# IC_DISPLAY_SCHE.net
KiCad netlist of a schematic drawn in Altium Designer
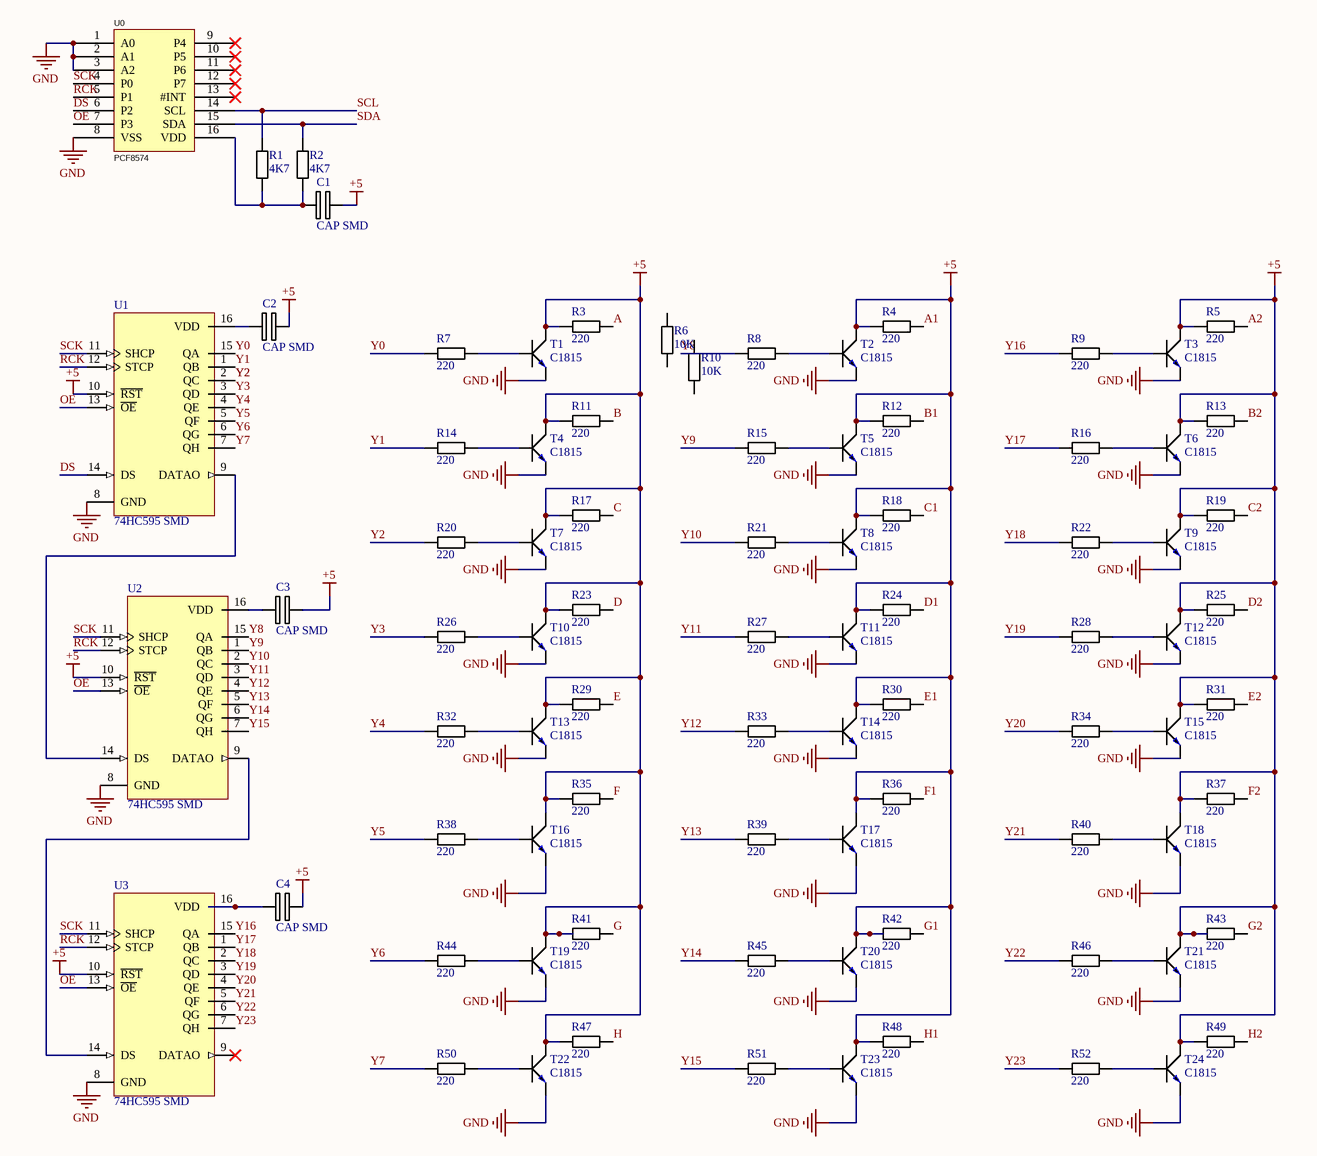
[diagram p0: IC_DISPLAY_SCHE.SchDoc]

(export (version "E")
  (design (tool "Eeschema 10.0.6"))
  (components
    (comp (ref "C1")
      (value "CAP SMD")
      (footprint "C-0805")
      (description "Capacitor Polarised")
      (fields
        (field (name "MANUFACTURER_PART_NUMBER") "TAJC227K006RNJV")
        (field (name "MOUSER PART NUMBER") "581-TAJC227K006RNJV")
      )
      (libsource (lib "MAIN1.2.3.4") (part "CAP SMD"))
    )
    (comp (ref "C2")
      (value "CAP SMD")
      (footprint "C-0805")
      (description "Capacitor Polarised")
      (fields
        (field (name "MANUFACTURER_PART_NUMBER") "TAJC227K006RNJV")
        (field (name "MOUSER PART NUMBER") "581-TAJC227K006RNJV")
      )
      (libsource (lib "MAIN1.2.3.4") (part "CAP SMD"))
    )
    (comp (ref "C3")
      (value "CAP SMD")
      (footprint "C-0805")
      (description "Capacitor Polarised")
      (fields
        (field (name "MANUFACTURER_PART_NUMBER") "TAJC227K006RNJV")
        (field (name "MOUSER PART NUMBER") "581-TAJC227K006RNJV")
      )
      (libsource (lib "MAIN1.2.3.4") (part "CAP SMD"))
    )
    (comp (ref "C4")
      (value "CAP SMD")
      (footprint "C-0805")
      (description "Capacitor Polarised")
      (fields
        (field (name "MANUFACTURER_PART_NUMBER") "TAJC227K006RNJV")
        (field (name "MOUSER PART NUMBER") "581-TAJC227K006RNJV")
      )
      (libsource (lib "MAIN1.2.3.4") (part "CAP SMD"))
    )
    (comp (ref "R1")
      (value "4K7")
      (footprint "Resistor 0805")
      (description "Resistor")
      (libsource (lib "MAIN1.2.3.4") (part "Resistor"))
    )
    (comp (ref "R2")
      (value "4K7")
      (footprint "Resistor 0805")
      (description "Resistor")
      (libsource (lib "MAIN1.2.3.4") (part "Resistor"))
    )
    (comp (ref "R3")
      (value "220")
      (footprint "Resistor 0805")
      (description "Resistor")
      (libsource (lib "MAIN1.2.3") (part "Resistor"))
    )
    (comp (ref "R4")
      (value "220")
      (footprint "Resistor 0805")
      (description "Resistor")
      (libsource (lib "MAIN1.2.3") (part "Resistor"))
    )
    (comp (ref "R5")
      (value "220")
      (footprint "Resistor 0805")
      (description "Resistor")
      (libsource (lib "MAIN1.2.3") (part "Resistor"))
    )
    (comp (ref "R6")
      (value "10K")
      (footprint "RES Axial 0.5W_10.16mm")
      (description "Resistor")
      (libsource (lib "MAIN1.2.3.4") (part "Resistor"))
    )
    (comp (ref "R7")
      (value "220")
      (footprint "Resistor 0805")
      (description "Resistor")
      (libsource (lib "MAIN1.2.3") (part "Resistor"))
    )
    (comp (ref "R8")
      (value "220")
      (footprint "Resistor 0805")
      (description "Resistor")
      (libsource (lib "MAIN1.2.3") (part "Resistor"))
    )
    (comp (ref "R9")
      (value "220")
      (footprint "Resistor 0805")
      (description "Resistor")
      (libsource (lib "MAIN1.2.3") (part "Resistor"))
    )
    (comp (ref "R10")
      (value "10K")
      (footprint "RES Axial 0.5W_10.16mm")
      (description "Resistor")
      (libsource (lib "MAIN1.2.3.4") (part "Resistor"))
    )
    (comp (ref "R11")
      (value "220")
      (footprint "Resistor 0805")
      (description "Resistor")
      (libsource (lib "MAIN1.2.3") (part "Resistor"))
    )
    (comp (ref "R12")
      (value "220")
      (footprint "Resistor 0805")
      (description "Resistor")
      (libsource (lib "MAIN1.2.3") (part "Resistor"))
    )
    (comp (ref "R13")
      (value "220")
      (footprint "Resistor 0805")
      (description "Resistor")
      (libsource (lib "MAIN1.2.3") (part "Resistor"))
    )
    (comp (ref "R14")
      (value "220")
      (footprint "Resistor 0805")
      (description "Resistor")
      (libsource (lib "MAIN1.2.3") (part "Resistor"))
    )
    (comp (ref "R15")
      (value "220")
      (footprint "Resistor 0805")
      (description "Resistor")
      (libsource (lib "MAIN1.2.3") (part "Resistor"))
    )
    (comp (ref "R16")
      (value "220")
      (footprint "Resistor 0805")
      (description "Resistor")
      (libsource (lib "MAIN1.2.3") (part "Resistor"))
    )
    (comp (ref "R17")
      (value "220")
      (footprint "Resistor 0805")
      (description "Resistor")
      (libsource (lib "MAIN1.2.3") (part "Resistor"))
    )
    (comp (ref "R18")
      (value "220")
      (footprint "Resistor 0805")
      (description "Resistor")
      (libsource (lib "MAIN1.2.3") (part "Resistor"))
    )
    (comp (ref "R19")
      (value "220")
      (footprint "Resistor 0805")
      (description "Resistor")
      (libsource (lib "MAIN1.2.3") (part "Resistor"))
    )
    (comp (ref "R20")
      (value "220")
      (footprint "Resistor 0805")
      (description "Resistor")
      (libsource (lib "MAIN1.2.3") (part "Resistor"))
    )
    (comp (ref "R21")
      (value "220")
      (footprint "Resistor 0805")
      (description "Resistor")
      (libsource (lib "MAIN1.2.3") (part "Resistor"))
    )
    (comp (ref "R22")
      (value "220")
      (footprint "Resistor 0805")
      (description "Resistor")
      (libsource (lib "MAIN1.2.3") (part "Resistor"))
    )
    (comp (ref "R23")
      (value "220")
      (footprint "Resistor 0805")
      (description "Resistor")
      (libsource (lib "MAIN1.2.3") (part "Resistor"))
    )
    (comp (ref "R24")
      (value "220")
      (footprint "Resistor 0805")
      (description "Resistor")
      (libsource (lib "MAIN1.2.3") (part "Resistor"))
    )
    (comp (ref "R25")
      (value "220")
      (footprint "Resistor 0805")
      (description "Resistor")
      (libsource (lib "MAIN1.2.3") (part "Resistor"))
    )
    (comp (ref "R26")
      (value "220")
      (footprint "Resistor 0805")
      (description "Resistor")
      (libsource (lib "MAIN1.2.3") (part "Resistor"))
    )
    (comp (ref "R27")
      (value "220")
      (footprint "Resistor 0805")
      (description "Resistor")
      (libsource (lib "MAIN1.2.3") (part "Resistor"))
    )
    (comp (ref "R28")
      (value "220")
      (footprint "Resistor 0805")
      (description "Resistor")
      (libsource (lib "MAIN1.2.3") (part "Resistor"))
    )
    (comp (ref "R29")
      (value "220")
      (footprint "Resistor 0805")
      (description "Resistor")
      (libsource (lib "MAIN1.2.3") (part "Resistor"))
    )
    (comp (ref "R30")
      (value "220")
      (footprint "Resistor 0805")
      (description "Resistor")
      (libsource (lib "MAIN1.2.3") (part "Resistor"))
    )
    (comp (ref "R31")
      (value "220")
      (footprint "Resistor 0805")
      (description "Resistor")
      (libsource (lib "MAIN1.2.3") (part "Resistor"))
    )
    (comp (ref "R32")
      (value "220")
      (footprint "Resistor 0805")
      (description "Resistor")
      (libsource (lib "MAIN1.2.3") (part "Resistor"))
    )
    (comp (ref "R33")
      (value "220")
      (footprint "Resistor 0805")
      (description "Resistor")
      (libsource (lib "MAIN1.2.3") (part "Resistor"))
    )
    (comp (ref "R34")
      (value "220")
      (footprint "Resistor 0805")
      (description "Resistor")
      (libsource (lib "MAIN1.2.3") (part "Resistor"))
    )
    (comp (ref "R35")
      (value "220")
      (footprint "Resistor 0805")
      (description "Resistor")
      (libsource (lib "MAIN1.2.3") (part "Resistor"))
    )
    (comp (ref "R36")
      (value "220")
      (footprint "Resistor 0805")
      (description "Resistor")
      (libsource (lib "MAIN1.2.3") (part "Resistor"))
    )
    (comp (ref "R37")
      (value "220")
      (footprint "Resistor 0805")
      (description "Resistor")
      (libsource (lib "MAIN1.2.3") (part "Resistor"))
    )
    (comp (ref "R38")
      (value "220")
      (footprint "Resistor 0805")
      (description "Resistor")
      (libsource (lib "MAIN1.2.3") (part "Resistor"))
    )
    (comp (ref "R39")
      (value "220")
      (footprint "Resistor 0805")
      (description "Resistor")
      (libsource (lib "MAIN1.2.3") (part "Resistor"))
    )
    (comp (ref "R40")
      (value "220")
      (footprint "Resistor 0805")
      (description "Resistor")
      (libsource (lib "MAIN1.2.3") (part "Resistor"))
    )
    (comp (ref "R41")
      (value "220")
      (footprint "Resistor 0805")
      (description "Resistor")
      (libsource (lib "MAIN1.2.3") (part "Resistor"))
    )
    (comp (ref "R42")
      (value "220")
      (footprint "Resistor 0805")
      (description "Resistor")
      (libsource (lib "MAIN1.2.3") (part "Resistor"))
    )
    (comp (ref "R43")
      (value "220")
      (footprint "Resistor 0805")
      (description "Resistor")
      (libsource (lib "MAIN1.2.3") (part "Resistor"))
    )
    (comp (ref "R44")
      (value "220")
      (footprint "Resistor 0805")
      (description "Resistor")
      (libsource (lib "MAIN1.2.3") (part "Resistor"))
    )
    (comp (ref "R45")
      (value "220")
      (footprint "Resistor 0805")
      (description "Resistor")
      (libsource (lib "MAIN1.2.3") (part "Resistor"))
    )
    (comp (ref "R46")
      (value "220")
      (footprint "Resistor 0805")
      (description "Resistor")
      (libsource (lib "MAIN1.2.3") (part "Resistor"))
    )
    (comp (ref "R47")
      (value "220")
      (footprint "Resistor 0805")
      (description "Resistor")
      (libsource (lib "MAIN1.2.3") (part "Resistor"))
    )
    (comp (ref "R48")
      (value "220")
      (footprint "Resistor 0805")
      (description "Resistor")
      (libsource (lib "MAIN1.2.3") (part "Resistor"))
    )
    (comp (ref "R49")
      (value "220")
      (footprint "Resistor 0805")
      (description "Resistor")
      (libsource (lib "MAIN1.2.3") (part "Resistor"))
    )
    (comp (ref "R50")
      (value "220")
      (footprint "Resistor 0805")
      (description "Resistor")
      (libsource (lib "MAIN1.2.3") (part "Resistor"))
    )
    (comp (ref "R51")
      (value "220")
      (footprint "Resistor 0805")
      (description "Resistor")
      (libsource (lib "MAIN1.2.3") (part "Resistor"))
    )
    (comp (ref "R52")
      (value "220")
      (footprint "Resistor 0805")
      (description "Resistor")
      (libsource (lib "MAIN1.2.3") (part "Resistor"))
    )
    (comp (ref "T1")
      (value "C1815")
      (footprint "SOT23-BCE")
      (description "Bipolar Transistors - BJT NPN Epitaxial Sil")
      (libsource (lib "MAIN1.2.3") (part "2SC1815"))
    )
    (comp (ref "T2")
      (value "C1815")
      (footprint "SOT23-BCE")
      (description "Bipolar Transistors - BJT NPN Epitaxial Sil")
      (libsource (lib "MAIN1.2.3") (part "2SC1815"))
    )
    (comp (ref "T3")
      (value "C1815")
      (footprint "SOT23-BCE")
      (description "Bipolar Transistors - BJT NPN Epitaxial Sil")
      (libsource (lib "MAIN1.2.3") (part "2SC1815"))
    )
    (comp (ref "T4")
      (value "C1815")
      (footprint "SOT23-BCE")
      (description "Bipolar Transistors - BJT NPN Epitaxial Sil")
      (libsource (lib "MAIN1.2.3") (part "2SC1815"))
    )
    (comp (ref "T5")
      (value "C1815")
      (footprint "SOT23-BCE")
      (description "Bipolar Transistors - BJT NPN Epitaxial Sil")
      (libsource (lib "MAIN1.2.3") (part "2SC1815"))
    )
    (comp (ref "T6")
      (value "C1815")
      (footprint "SOT23-BCE")
      (description "Bipolar Transistors - BJT NPN Epitaxial Sil")
      (libsource (lib "MAIN1.2.3") (part "2SC1815"))
    )
    (comp (ref "T7")
      (value "C1815")
      (footprint "SOT23-BCE")
      (description "Bipolar Transistors - BJT NPN Epitaxial Sil")
      (libsource (lib "MAIN1.2.3") (part "2SC1815"))
    )
    (comp (ref "T8")
      (value "C1815")
      (footprint "SOT23-BCE")
      (description "Bipolar Transistors - BJT NPN Epitaxial Sil")
      (libsource (lib "MAIN1.2.3") (part "2SC1815"))
    )
    (comp (ref "T9")
      (value "C1815")
      (footprint "SOT23-BCE")
      (description "Bipolar Transistors - BJT NPN Epitaxial Sil")
      (libsource (lib "MAIN1.2.3") (part "2SC1815"))
    )
    (comp (ref "T10")
      (value "C1815")
      (footprint "SOT23-BCE")
      (description "Bipolar Transistors - BJT NPN Epitaxial Sil")
      (libsource (lib "MAIN1.2.3") (part "2SC1815"))
    )
    (comp (ref "T11")
      (value "C1815")
      (footprint "SOT23-BCE")
      (description "Bipolar Transistors - BJT NPN Epitaxial Sil")
      (libsource (lib "MAIN1.2.3") (part "2SC1815"))
    )
    (comp (ref "T12")
      (value "C1815")
      (footprint "SOT23-BCE")
      (description "Bipolar Transistors - BJT NPN Epitaxial Sil")
      (libsource (lib "MAIN1.2.3") (part "2SC1815"))
    )
    (comp (ref "T13")
      (value "C1815")
      (footprint "SOT23-BCE")
      (description "Bipolar Transistors - BJT NPN Epitaxial Sil")
      (libsource (lib "MAIN1.2.3") (part "2SC1815"))
    )
    (comp (ref "T14")
      (value "C1815")
      (footprint "SOT23-BCE")
      (description "Bipolar Transistors - BJT NPN Epitaxial Sil")
      (libsource (lib "MAIN1.2.3") (part "2SC1815"))
    )
    (comp (ref "T15")
      (value "C1815")
      (footprint "SOT23-BCE")
      (description "Bipolar Transistors - BJT NPN Epitaxial Sil")
      (libsource (lib "MAIN1.2.3") (part "2SC1815"))
    )
    (comp (ref "T16")
      (value "C1815")
      (footprint "SOT23-BCE")
      (description "Bipolar Transistors - BJT NPN Epitaxial Sil")
      (libsource (lib "MAIN1.2.3") (part "2SC1815"))
    )
    (comp (ref "T17")
      (value "C1815")
      (footprint "SOT23-BCE")
      (description "Bipolar Transistors - BJT NPN Epitaxial Sil")
      (libsource (lib "MAIN1.2.3") (part "2SC1815"))
    )
    (comp (ref "T18")
      (value "C1815")
      (footprint "SOT23-BCE")
      (description "Bipolar Transistors - BJT NPN Epitaxial Sil")
      (libsource (lib "MAIN1.2.3") (part "2SC1815"))
    )
    (comp (ref "T19")
      (value "C1815")
      (footprint "SOT23-BCE")
      (description "Bipolar Transistors - BJT NPN Epitaxial Sil")
      (libsource (lib "MAIN1.2.3") (part "2SC1815"))
    )
    (comp (ref "T20")
      (value "C1815")
      (footprint "SOT23-BCE")
      (description "Bipolar Transistors - BJT NPN Epitaxial Sil")
      (libsource (lib "MAIN1.2.3") (part "2SC1815"))
    )
    (comp (ref "T21")
      (value "C1815")
      (footprint "SOT23-BCE")
      (description "Bipolar Transistors - BJT NPN Epitaxial Sil")
      (libsource (lib "MAIN1.2.3") (part "2SC1815"))
    )
    (comp (ref "T22")
      (value "C1815")
      (footprint "SOT23-BCE")
      (description "Bipolar Transistors - BJT NPN Epitaxial Sil")
      (libsource (lib "MAIN1.2.3") (part "2SC1815"))
    )
    (comp (ref "T23")
      (value "C1815")
      (footprint "SOT23-BCE")
      (description "Bipolar Transistors - BJT NPN Epitaxial Sil")
      (libsource (lib "MAIN1.2.3") (part "2SC1815"))
    )
    (comp (ref "T24")
      (value "C1815")
      (footprint "SOT23-BCE")
      (description "Bipolar Transistors - BJT NPN Epitaxial Sil")
      (libsource (lib "MAIN1.2.3") (part "2SC1815"))
    )
    (comp (ref "U0")
      (value "PCF8574")
      (footprint "SOIC-16-pcf8574")
      (fields (field (name "MANUFACTURER") "NXP(恩智浦)") (field (name "MANUFACTURER PART") "PCF8574AT/3,518"))
      (libsource (lib "MAIN1.2.3.4") (part "PCF8574AT/3"))
    )
    (comp (ref "U1")
      (value "74HC595 SMD")
      (footprint "SOP 16")
      (description "Dán")
      (libsource (lib "Altium_Lib_by_KhueNguyenCreator") (part "74HC595 SMD"))
    )
    (comp (ref "U2")
      (value "74HC595 SMD")
      (footprint "SOP 16")
      (description "Dán")
      (libsource (lib "Altium_Lib_by_KhueNguyenCreator") (part "74HC595 SMD"))
    )
    (comp (ref "U3")
      (value "74HC595 SMD")
      (footprint "SOP 16")
      (description "Dán")
      (libsource (lib "Altium_Lib_by_KhueNguyenCreator") (part "74HC595 SMD"))
    )
  )
  (nets
    (net (code "1") (name "+5") (class "Default")
      (node (ref "C1") (pin "2") (pinfunction "-_2") (pintype "passive"))
      (node (ref "C2") (pin "2") (pinfunction "-_2") (pintype "passive"))
      (node (ref "C3") (pin "2") (pinfunction "-_2") (pintype "passive"))
      (node (ref "C4") (pin "2") (pinfunction "-_2") (pintype "passive"))
      (node (ref "R11") (pin "2") (pinfunction "2_2") (pintype "passive"))
      (node (ref "R12") (pin "2") (pinfunction "2_2") (pintype "passive"))
      (node (ref "R13") (pin "2") (pinfunction "2_2") (pintype "passive"))
      (node (ref "R17") (pin "2") (pinfunction "2_2") (pintype "passive"))
      (node (ref "R18") (pin "2") (pinfunction "2_2") (pintype "passive"))
      (node (ref "R19") (pin "2") (pinfunction "2_2") (pintype "passive"))
      (node (ref "R23") (pin "2") (pinfunction "2_2") (pintype "passive"))
      (node (ref "R24") (pin "2") (pinfunction "2_2") (pintype "passive"))
      (node (ref "R25") (pin "2") (pinfunction "2_2") (pintype "passive"))
      (node (ref "R29") (pin "2") (pinfunction "2_2") (pintype "passive"))
      (node (ref "R3") (pin "2") (pinfunction "2_2") (pintype "passive"))
      (node (ref "R30") (pin "2") (pinfunction "2_2") (pintype "passive"))
      (node (ref "R31") (pin "2") (pinfunction "2_2") (pintype "passive"))
      (node (ref "R35") (pin "2") (pinfunction "2_2") (pintype "passive"))
      (node (ref "R36") (pin "2") (pinfunction "2_2") (pintype "passive"))
      (node (ref "R37") (pin "2") (pinfunction "2_2") (pintype "passive"))
      (node (ref "R4") (pin "2") (pinfunction "2_2") (pintype "passive"))
      (node (ref "R41") (pin "2") (pinfunction "2_2") (pintype "passive"))
      (node (ref "R42") (pin "2") (pinfunction "2_2") (pintype "passive"))
      (node (ref "R43") (pin "2") (pinfunction "2_2") (pintype "passive"))
      (node (ref "R47") (pin "2") (pinfunction "2_2") (pintype "passive"))
      (node (ref "R48") (pin "2") (pinfunction "2_2") (pintype "passive"))
      (node (ref "R49") (pin "2") (pinfunction "2_2") (pintype "passive"))
      (node (ref "R5") (pin "2") (pinfunction "2_2") (pintype "passive"))
      (node (ref "T1") (pin "2") (pinfunction "C_2") (pintype "passive"))
      (node (ref "T10") (pin "2") (pinfunction "C_2") (pintype "passive"))
      (node (ref "T11") (pin "2") (pinfunction "C_2") (pintype "passive"))
      (node (ref "T12") (pin "2") (pinfunction "C_2") (pintype "passive"))
      (node (ref "T13") (pin "2") (pinfunction "C_2") (pintype "passive"))
      (node (ref "T14") (pin "2") (pinfunction "C_2") (pintype "passive"))
      (node (ref "T15") (pin "2") (pinfunction "C_2") (pintype "passive"))
      (node (ref "T16") (pin "2") (pinfunction "C_2") (pintype "passive"))
      (node (ref "T17") (pin "2") (pinfunction "C_2") (pintype "passive"))
      (node (ref "T18") (pin "2") (pinfunction "C_2") (pintype "passive"))
      (node (ref "T19") (pin "2") (pinfunction "C_2") (pintype "passive"))
      (node (ref "T2") (pin "2") (pinfunction "C_2") (pintype "passive"))
      (node (ref "T20") (pin "2") (pinfunction "C_2") (pintype "passive"))
      (node (ref "T21") (pin "2") (pinfunction "C_2") (pintype "passive"))
      (node (ref "T22") (pin "2") (pinfunction "C_2") (pintype "passive"))
      (node (ref "T23") (pin "2") (pinfunction "C_2") (pintype "passive"))
      (node (ref "T24") (pin "2") (pinfunction "C_2") (pintype "passive"))
      (node (ref "T3") (pin "2") (pinfunction "C_2") (pintype "passive"))
      (node (ref "T4") (pin "2") (pinfunction "C_2") (pintype "passive"))
      (node (ref "T5") (pin "2") (pinfunction "C_2") (pintype "passive"))
      (node (ref "T6") (pin "2") (pinfunction "C_2") (pintype "passive"))
      (node (ref "T7") (pin "2") (pinfunction "C_2") (pintype "passive"))
      (node (ref "T8") (pin "2") (pinfunction "C_2") (pintype "passive"))
      (node (ref "T9") (pin "2") (pinfunction "C_2") (pintype "passive"))
      (node (ref "U1") (pin "10") (pinfunction "~{RST}_10") (pintype "input"))
      (node (ref "U2") (pin "10") (pinfunction "~{RST}_10") (pintype "input"))
      (node (ref "U3") (pin "10") (pinfunction "~{RST}_10") (pintype "input"))
    )
    (net (code "2") (name "/A") (class "Default")
      (node (ref "R3") (pin "1") (pinfunction "1_1") (pintype "passive"))
    )
    (net (code "3") (name "/A1") (class "Default")
      (node (ref "R4") (pin "1") (pinfunction "1_1") (pintype "passive"))
    )
    (net (code "4") (name "/A2") (class "Default")
      (node (ref "R5") (pin "1") (pinfunction "1_1") (pintype "passive"))
    )
    (net (code "5") (name "/B") (class "Default")
      (node (ref "R11") (pin "1") (pinfunction "1_1") (pintype "passive"))
    )
    (net (code "6") (name "/B1") (class "Default")
      (node (ref "R12") (pin "1") (pinfunction "1_1") (pintype "passive"))
    )
    (net (code "7") (name "/B2") (class "Default")
      (node (ref "R13") (pin "1") (pinfunction "1_1") (pintype "passive"))
    )
    (net (code "8") (name "/C") (class "Default")
      (node (ref "R17") (pin "1") (pinfunction "1_1") (pintype "passive"))
    )
    (net (code "9") (name "/C1") (class "Default")
      (node (ref "R18") (pin "1") (pinfunction "1_1") (pintype "passive"))
    )
    (net (code "10") (name "/C2") (class "Default")
      (node (ref "R19") (pin "1") (pinfunction "1_1") (pintype "passive"))
    )
    (net (code "11") (name "/D") (class "Default")
      (node (ref "R23") (pin "1") (pinfunction "1_1") (pintype "passive"))
    )
    (net (code "12") (name "/D1") (class "Default")
      (node (ref "R24") (pin "1") (pinfunction "1_1") (pintype "passive"))
    )
    (net (code "13") (name "/D2") (class "Default")
      (node (ref "R25") (pin "1") (pinfunction "1_1") (pintype "passive"))
    )
    (net (code "14") (name "/DS") (class "Default")
      (node (ref "U0") (pin "6") (pinfunction "P2_6") (pintype "passive"))
      (node (ref "U1") (pin "14") (pinfunction "DS_14") (pintype "input"))
    )
    (net (code "15") (name "/E") (class "Default")
      (node (ref "R29") (pin "1") (pinfunction "1_1") (pintype "passive"))
    )
    (net (code "16") (name "/E1") (class "Default")
      (node (ref "R30") (pin "1") (pinfunction "1_1") (pintype "passive"))
    )
    (net (code "17") (name "/E2") (class "Default")
      (node (ref "R31") (pin "1") (pinfunction "1_1") (pintype "passive"))
    )
    (net (code "18") (name "/F") (class "Default")
      (node (ref "R35") (pin "1") (pinfunction "1_1") (pintype "passive"))
    )
    (net (code "19") (name "/F1") (class "Default")
      (node (ref "R36") (pin "1") (pinfunction "1_1") (pintype "passive"))
    )
    (net (code "20") (name "/F2") (class "Default")
      (node (ref "R37") (pin "1") (pinfunction "1_1") (pintype "passive"))
    )
    (net (code "21") (name "/G") (class "Default")
      (node (ref "R41") (pin "1") (pinfunction "1_1") (pintype "passive"))
    )
    (net (code "22") (name "/G1") (class "Default")
      (node (ref "R42") (pin "1") (pinfunction "1_1") (pintype "passive"))
    )
    (net (code "23") (name "/G2") (class "Default")
      (node (ref "R43") (pin "1") (pinfunction "1_1") (pintype "passive"))
    )
    (net (code "24") (name "/H") (class "Default")
      (node (ref "R47") (pin "1") (pinfunction "1_1") (pintype "passive"))
    )
    (net (code "25") (name "/H1") (class "Default")
      (node (ref "R48") (pin "1") (pinfunction "1_1") (pintype "passive"))
    )
    (net (code "26") (name "/H2") (class "Default")
      (node (ref "R49") (pin "1") (pinfunction "1_1") (pintype "passive"))
    )
    (net (code "27") (name "/OE") (class "Default")
      (node (ref "U0") (pin "7") (pinfunction "P3_7") (pintype "passive"))
      (node (ref "U1") (pin "13") (pinfunction "~{OE}_13") (pintype "input"))
      (node (ref "U2") (pin "13") (pinfunction "~{OE}_13") (pintype "input"))
      (node (ref "U3") (pin "13") (pinfunction "~{OE}_13") (pintype "input"))
    )
    (net (code "28") (name "/RCK") (class "Default")
      (node (ref "U0") (pin "5") (pinfunction "P1_5") (pintype "passive"))
      (node (ref "U1") (pin "12") (pinfunction "STCP_12") (pintype "input"))
      (node (ref "U2") (pin "12") (pinfunction "STCP_12") (pintype "input"))
      (node (ref "U3") (pin "12") (pinfunction "STCP_12") (pintype "input"))
    )
    (net (code "29") (name "/SCK") (class "Default")
      (node (ref "U0") (pin "4") (pinfunction "P0_4") (pintype "passive"))
      (node (ref "U1") (pin "11") (pinfunction "SHCP_11") (pintype "input"))
      (node (ref "U2") (pin "11") (pinfunction "SHCP_11") (pintype "input"))
      (node (ref "U3") (pin "11") (pinfunction "SHCP_11") (pintype "input"))
    )
    (net (code "30") (name "/SCL") (class "Default")
      (node (ref "R1") (pin "2") (pinfunction "2_2") (pintype "passive"))
      (node (ref "U0") (pin "14") (pinfunction "SCL_14") (pintype "passive"))
    )
    (net (code "31") (name "/SDA") (class "Default")
      (node (ref "R2") (pin "2") (pinfunction "2_2") (pintype "passive"))
      (node (ref "U0") (pin "15") (pinfunction "SDA_15") (pintype "passive"))
    )
    (net (code "32") (name "/Y0") (class "Default")
      (node (ref "R7") (pin "2") (pinfunction "2_2") (pintype "passive"))
      (node (ref "U1") (pin "15") (pinfunction "QA_15") (pintype "tri_state"))
    )
    (net (code "33") (name "/Y1") (class "Default")
      (node (ref "R14") (pin "2") (pinfunction "2_2") (pintype "passive"))
      (node (ref "U1") (pin "1") (pinfunction "QB_1") (pintype "tri_state"))
    )
    (net (code "34") (name "/Y2") (class "Default")
      (node (ref "R20") (pin "2") (pinfunction "2_2") (pintype "passive"))
      (node (ref "U1") (pin "2") (pinfunction "QC_2") (pintype "tri_state"))
    )
    (net (code "35") (name "/Y3") (class "Default")
      (node (ref "R26") (pin "2") (pinfunction "2_2") (pintype "passive"))
      (node (ref "U1") (pin "3") (pinfunction "QD_3") (pintype "tri_state"))
    )
    (net (code "36") (name "/Y4") (class "Default")
      (node (ref "R32") (pin "2") (pinfunction "2_2") (pintype "passive"))
      (node (ref "U1") (pin "4") (pinfunction "QE_4") (pintype "tri_state"))
    )
    (net (code "37") (name "/Y5") (class "Default")
      (node (ref "R38") (pin "2") (pinfunction "2_2") (pintype "passive"))
      (node (ref "U1") (pin "5") (pinfunction "QF_5") (pintype "tri_state"))
    )
    (net (code "38") (name "/Y6") (class "Default")
      (node (ref "R44") (pin "2") (pinfunction "2_2") (pintype "passive"))
      (node (ref "U1") (pin "6") (pinfunction "QG_6") (pintype "tri_state"))
    )
    (net (code "39") (name "/Y7") (class "Default")
      (node (ref "R50") (pin "2") (pinfunction "2_2") (pintype "passive"))
      (node (ref "U1") (pin "7") (pinfunction "QH_7") (pintype "tri_state"))
    )
    (net (code "40") (name "/Y8") (class "Default")
      (node (ref "R8") (pin "2") (pinfunction "2_2") (pintype "passive"))
      (node (ref "U2") (pin "15") (pinfunction "QA_15") (pintype "tri_state"))
    )
    (net (code "41") (name "/Y9") (class "Default")
      (node (ref "R15") (pin "2") (pinfunction "2_2") (pintype "passive"))
      (node (ref "U2") (pin "1") (pinfunction "QB_1") (pintype "tri_state"))
    )
    (net (code "42") (name "/Y10") (class "Default")
      (node (ref "R21") (pin "2") (pinfunction "2_2") (pintype "passive"))
      (node (ref "U2") (pin "2") (pinfunction "QC_2") (pintype "tri_state"))
    )
    (net (code "43") (name "/Y11") (class "Default")
      (node (ref "R27") (pin "2") (pinfunction "2_2") (pintype "passive"))
      (node (ref "U2") (pin "3") (pinfunction "QD_3") (pintype "tri_state"))
    )
    (net (code "44") (name "/Y12") (class "Default")
      (node (ref "R33") (pin "2") (pinfunction "2_2") (pintype "passive"))
      (node (ref "U2") (pin "4") (pinfunction "QE_4") (pintype "tri_state"))
    )
    (net (code "45") (name "/Y13") (class "Default")
      (node (ref "R39") (pin "2") (pinfunction "2_2") (pintype "passive"))
      (node (ref "U2") (pin "5") (pinfunction "QF_5") (pintype "tri_state"))
    )
    (net (code "46") (name "/Y14") (class "Default")
      (node (ref "R45") (pin "2") (pinfunction "2_2") (pintype "passive"))
      (node (ref "U2") (pin "6") (pinfunction "QG_6") (pintype "tri_state"))
    )
    (net (code "47") (name "/Y15") (class "Default")
      (node (ref "R51") (pin "2") (pinfunction "2_2") (pintype "passive"))
      (node (ref "U2") (pin "7") (pinfunction "QH_7") (pintype "tri_state"))
    )
    (net (code "48") (name "/Y16") (class "Default")
      (node (ref "R9") (pin "2") (pinfunction "2_2") (pintype "passive"))
      (node (ref "U3") (pin "15") (pinfunction "QA_15") (pintype "tri_state"))
    )
    (net (code "49") (name "/Y17") (class "Default")
      (node (ref "R16") (pin "2") (pinfunction "2_2") (pintype "passive"))
      (node (ref "U3") (pin "1") (pinfunction "QB_1") (pintype "tri_state"))
    )
    (net (code "50") (name "/Y18") (class "Default")
      (node (ref "R22") (pin "2") (pinfunction "2_2") (pintype "passive"))
      (node (ref "U3") (pin "2") (pinfunction "QC_2") (pintype "tri_state"))
    )
    (net (code "51") (name "/Y19") (class "Default")
      (node (ref "R28") (pin "2") (pinfunction "2_2") (pintype "passive"))
      (node (ref "U3") (pin "3") (pinfunction "QD_3") (pintype "tri_state"))
    )
    (net (code "52") (name "/Y20") (class "Default")
      (node (ref "R34") (pin "2") (pinfunction "2_2") (pintype "passive"))
      (node (ref "U3") (pin "4") (pinfunction "QE_4") (pintype "tri_state"))
    )
    (net (code "53") (name "/Y21") (class "Default")
      (node (ref "R40") (pin "2") (pinfunction "2_2") (pintype "passive"))
      (node (ref "U3") (pin "5") (pinfunction "QF_5") (pintype "tri_state"))
    )
    (net (code "54") (name "/Y22") (class "Default")
      (node (ref "R46") (pin "2") (pinfunction "2_2") (pintype "passive"))
      (node (ref "U3") (pin "6") (pinfunction "QG_6") (pintype "tri_state"))
    )
    (net (code "55") (name "/Y23") (class "Default")
      (node (ref "R52") (pin "2") (pinfunction "2_2") (pintype "passive"))
      (node (ref "U3") (pin "7") (pinfunction "QH_7") (pintype "tri_state"))
    )
    (net (code "56") (name "GND") (class "Default")
      (node (ref "T1") (pin "3") (pinfunction "E_3") (pintype "passive"))
      (node (ref "T10") (pin "3") (pinfunction "E_3") (pintype "passive"))
      (node (ref "T11") (pin "3") (pinfunction "E_3") (pintype "passive"))
      (node (ref "T12") (pin "3") (pinfunction "E_3") (pintype "passive"))
      (node (ref "T13") (pin "3") (pinfunction "E_3") (pintype "passive"))
      (node (ref "T14") (pin "3") (pinfunction "E_3") (pintype "passive"))
      (node (ref "T15") (pin "3") (pinfunction "E_3") (pintype "passive"))
      (node (ref "T16") (pin "3") (pinfunction "E_3") (pintype "passive"))
      (node (ref "T17") (pin "3") (pinfunction "E_3") (pintype "passive"))
      (node (ref "T18") (pin "3") (pinfunction "E_3") (pintype "passive"))
      (node (ref "T19") (pin "3") (pinfunction "E_3") (pintype "passive"))
      (node (ref "T2") (pin "3") (pinfunction "E_3") (pintype "passive"))
      (node (ref "T20") (pin "3") (pinfunction "E_3") (pintype "passive"))
      (node (ref "T21") (pin "3") (pinfunction "E_3") (pintype "passive"))
      (node (ref "T22") (pin "3") (pinfunction "E_3") (pintype "passive"))
      (node (ref "T23") (pin "3") (pinfunction "E_3") (pintype "passive"))
      (node (ref "T24") (pin "3") (pinfunction "E_3") (pintype "passive"))
      (node (ref "T3") (pin "3") (pinfunction "E_3") (pintype "passive"))
      (node (ref "T4") (pin "3") (pinfunction "E_3") (pintype "passive"))
      (node (ref "T5") (pin "3") (pinfunction "E_3") (pintype "passive"))
      (node (ref "T6") (pin "3") (pinfunction "E_3") (pintype "passive"))
      (node (ref "T7") (pin "3") (pinfunction "E_3") (pintype "passive"))
      (node (ref "T8") (pin "3") (pinfunction "E_3") (pintype "passive"))
      (node (ref "T9") (pin "3") (pinfunction "E_3") (pintype "passive"))
      (node (ref "U0") (pin "1") (pinfunction "A0_1") (pintype "passive"))
      (node (ref "U0") (pin "2") (pinfunction "A1_2") (pintype "passive"))
      (node (ref "U0") (pin "3") (pinfunction "A2_3") (pintype "passive"))
      (node (ref "U0") (pin "8") (pinfunction "VSS_8") (pintype "passive"))
      (node (ref "U1") (pin "8") (pinfunction "GND_8") (pintype "power_in"))
      (node (ref "U2") (pin "8") (pinfunction "GND_8") (pintype "power_in"))
      (node (ref "U3") (pin "8") (pinfunction "GND_8") (pintype "power_in"))
    )
    (net (code "57") (name "Net-(C1-+)") (class "Default")
      (node (ref "C1") (pin "1") (pinfunction "+_1") (pintype "passive"))
      (node (ref "R1") (pin "1") (pinfunction "1_1") (pintype "passive"))
      (node (ref "R2") (pin "1") (pinfunction "1_1") (pintype "passive"))
      (node (ref "U0") (pin "16") (pinfunction "VDD_16") (pintype "passive"))
    )
    (net (code "58") (name "Net-(C2-+)") (class "Default")
      (node (ref "C2") (pin "1") (pinfunction "+_1") (pintype "passive"))
      (node (ref "U1") (pin "16") (pinfunction "VDD_16") (pintype "power_in"))
    )
    (net (code "59") (name "Net-(C3-+)") (class "Default")
      (node (ref "C3") (pin "1") (pinfunction "+_1") (pintype "passive"))
      (node (ref "U2") (pin "16") (pinfunction "VDD_16") (pintype "power_in"))
    )
    (net (code "60") (name "Net-(C4-+)") (class "Default")
      (node (ref "C4") (pin "1") (pinfunction "+_1") (pintype "passive"))
      (node (ref "U3") (pin "16") (pinfunction "VDD_16") (pintype "power_in"))
    )
    (net (code "61") (name "Net-(T1-B)") (class "Default")
      (node (ref "R7") (pin "1") (pinfunction "1_1") (pintype "passive"))
      (node (ref "T1") (pin "1") (pinfunction "B_1") (pintype "passive"))
    )
    (net (code "62") (name "Net-(T2-B)") (class "Default")
      (node (ref "R8") (pin "1") (pinfunction "1_1") (pintype "passive"))
      (node (ref "T2") (pin "1") (pinfunction "B_1") (pintype "passive"))
    )
    (net (code "63") (name "Net-(T3-B)") (class "Default")
      (node (ref "R9") (pin "1") (pinfunction "1_1") (pintype "passive"))
      (node (ref "T3") (pin "1") (pinfunction "B_1") (pintype "passive"))
    )
    (net (code "64") (name "Net-(T4-B)") (class "Default")
      (node (ref "R14") (pin "1") (pinfunction "1_1") (pintype "passive"))
      (node (ref "T4") (pin "1") (pinfunction "B_1") (pintype "passive"))
    )
    (net (code "65") (name "Net-(T5-B)") (class "Default")
      (node (ref "R15") (pin "1") (pinfunction "1_1") (pintype "passive"))
      (node (ref "T5") (pin "1") (pinfunction "B_1") (pintype "passive"))
    )
    (net (code "66") (name "Net-(T6-B)") (class "Default")
      (node (ref "R16") (pin "1") (pinfunction "1_1") (pintype "passive"))
      (node (ref "T6") (pin "1") (pinfunction "B_1") (pintype "passive"))
    )
    (net (code "67") (name "Net-(T7-B)") (class "Default")
      (node (ref "R20") (pin "1") (pinfunction "1_1") (pintype "passive"))
      (node (ref "T7") (pin "1") (pinfunction "B_1") (pintype "passive"))
    )
    (net (code "68") (name "Net-(T8-B)") (class "Default")
      (node (ref "R21") (pin "1") (pinfunction "1_1") (pintype "passive"))
      (node (ref "T8") (pin "1") (pinfunction "B_1") (pintype "passive"))
    )
    (net (code "69") (name "Net-(T9-B)") (class "Default")
      (node (ref "R22") (pin "1") (pinfunction "1_1") (pintype "passive"))
      (node (ref "T9") (pin "1") (pinfunction "B_1") (pintype "passive"))
    )
    (net (code "70") (name "Net-(T10-B)") (class "Default")
      (node (ref "R26") (pin "1") (pinfunction "1_1") (pintype "passive"))
      (node (ref "T10") (pin "1") (pinfunction "B_1") (pintype "passive"))
    )
    (net (code "71") (name "Net-(T11-B)") (class "Default")
      (node (ref "R27") (pin "1") (pinfunction "1_1") (pintype "passive"))
      (node (ref "T11") (pin "1") (pinfunction "B_1") (pintype "passive"))
    )
    (net (code "72") (name "Net-(T12-B)") (class "Default")
      (node (ref "R28") (pin "1") (pinfunction "1_1") (pintype "passive"))
      (node (ref "T12") (pin "1") (pinfunction "B_1") (pintype "passive"))
    )
    (net (code "73") (name "Net-(T13-B)") (class "Default")
      (node (ref "R32") (pin "1") (pinfunction "1_1") (pintype "passive"))
      (node (ref "T13") (pin "1") (pinfunction "B_1") (pintype "passive"))
    )
    (net (code "74") (name "Net-(T14-B)") (class "Default")
      (node (ref "R33") (pin "1") (pinfunction "1_1") (pintype "passive"))
      (node (ref "T14") (pin "1") (pinfunction "B_1") (pintype "passive"))
    )
    (net (code "75") (name "Net-(T15-B)") (class "Default")
      (node (ref "R34") (pin "1") (pinfunction "1_1") (pintype "passive"))
      (node (ref "T15") (pin "1") (pinfunction "B_1") (pintype "passive"))
    )
    (net (code "76") (name "Net-(T16-B)") (class "Default")
      (node (ref "R38") (pin "1") (pinfunction "1_1") (pintype "passive"))
      (node (ref "T16") (pin "1") (pinfunction "B_1") (pintype "passive"))
    )
    (net (code "77") (name "Net-(T17-B)") (class "Default")
      (node (ref "R39") (pin "1") (pinfunction "1_1") (pintype "passive"))
      (node (ref "T17") (pin "1") (pinfunction "B_1") (pintype "passive"))
    )
    (net (code "78") (name "Net-(T18-B)") (class "Default")
      (node (ref "R40") (pin "1") (pinfunction "1_1") (pintype "passive"))
      (node (ref "T18") (pin "1") (pinfunction "B_1") (pintype "passive"))
    )
    (net (code "79") (name "Net-(T19-B)") (class "Default")
      (node (ref "R44") (pin "1") (pinfunction "1_1") (pintype "passive"))
      (node (ref "T19") (pin "1") (pinfunction "B_1") (pintype "passive"))
    )
    (net (code "80") (name "Net-(T20-B)") (class "Default")
      (node (ref "R45") (pin "1") (pinfunction "1_1") (pintype "passive"))
      (node (ref "T20") (pin "1") (pinfunction "B_1") (pintype "passive"))
    )
    (net (code "81") (name "Net-(T21-B)") (class "Default")
      (node (ref "R46") (pin "1") (pinfunction "1_1") (pintype "passive"))
      (node (ref "T21") (pin "1") (pinfunction "B_1") (pintype "passive"))
    )
    (net (code "82") (name "Net-(T22-B)") (class "Default")
      (node (ref "R50") (pin "1") (pinfunction "1_1") (pintype "passive"))
      (node (ref "T22") (pin "1") (pinfunction "B_1") (pintype "passive"))
    )
    (net (code "83") (name "Net-(T23-B)") (class "Default")
      (node (ref "R51") (pin "1") (pinfunction "1_1") (pintype "passive"))
      (node (ref "T23") (pin "1") (pinfunction "B_1") (pintype "passive"))
    )
    (net (code "84") (name "Net-(T24-B)") (class "Default")
      (node (ref "R52") (pin "1") (pinfunction "1_1") (pintype "passive"))
      (node (ref "T24") (pin "1") (pinfunction "B_1") (pintype "passive"))
    )
    (net (code "85") (name "Net-(U1-DATAO)") (class "Default")
      (node (ref "U1") (pin "9") (pinfunction "DATAO_9") (pintype "output"))
      (node (ref "U2") (pin "14") (pinfunction "DS_14") (pintype "input"))
    )
    (net (code "86") (name "Net-(U2-DATAO)") (class "Default")
      (node (ref "U2") (pin "9") (pinfunction "DATAO_9") (pintype "output"))
      (node (ref "U3") (pin "14") (pinfunction "DS_14") (pintype "input"))
    )
    (net (code "87") (name "unconnected-(R6-Pad1)") (class "Default")
      (node (ref "R6") (pin "1") (pinfunction "1_1") (pintype "passive"))
    )
    (net (code "88") (name "unconnected-(R6-Pad2)") (class "Default")
      (node (ref "R6") (pin "2") (pinfunction "2_2") (pintype "passive"))
    )
    (net (code "89") (name "unconnected-(R10-Pad1)") (class "Default")
      (node (ref "R10") (pin "1") (pinfunction "1_1") (pintype "passive"))
    )
    (net (code "90") (name "unconnected-(R10-Pad2)") (class "Default")
      (node (ref "R10") (pin "2") (pinfunction "2_2") (pintype "passive"))
    )
    (net (code "91") (name "unconnected-(U0-#INT-Pad13)") (class "Default")
      (node (ref "U0") (pin "13") (pinfunction "#INT_13") (pintype "passive+no_connect"))
    )
    (net (code "92") (name "unconnected-(U0-P4-Pad9)") (class "Default")
      (node (ref "U0") (pin "9") (pinfunction "P4_9") (pintype "passive+no_connect"))
    )
    (net (code "93") (name "unconnected-(U0-P5-Pad10)") (class "Default")
      (node (ref "U0") (pin "10") (pinfunction "P5_10") (pintype "passive+no_connect"))
    )
    (net (code "94") (name "unconnected-(U0-P6-Pad11)") (class "Default")
      (node (ref "U0") (pin "11") (pinfunction "P6_11") (pintype "passive+no_connect"))
    )
    (net (code "95") (name "unconnected-(U0-P7-Pad12)") (class "Default")
      (node (ref "U0") (pin "12") (pinfunction "P7_12") (pintype "passive+no_connect"))
    )
    (net (code "96") (name "unconnected-(U3-DATAO-Pad9)") (class "Default")
      (node (ref "U3") (pin "9") (pinfunction "DATAO_9") (pintype "output+no_connect"))
    )
  )
)
